# Analog_Controller_PCB.net
KiCad netlist of a schematic drawn in EAGLE
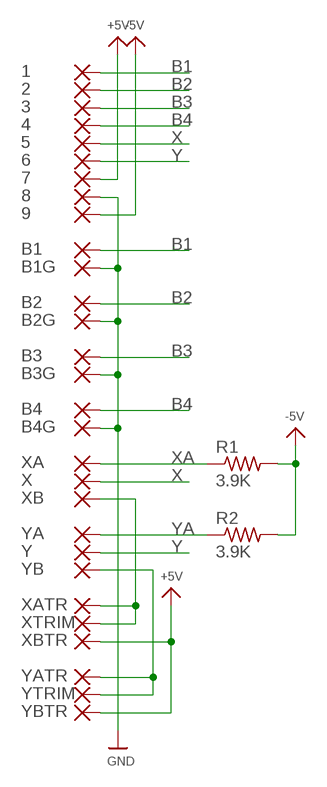
[diagram p0: schematic, sheet 1]

(export (version "E")
  (design (tool "Eeschema 10.0.6"))
  (components
    (comp (ref "1")
      (value "SMD2")
      (footprint "eagle-import:SMD1,27-2,54")
      (libsource (lib "eagle-import") (part "SMD2"))
    )
    (comp (ref "2")
      (value "SMD2")
      (footprint "eagle-import:SMD1,27-2,54")
      (libsource (lib "eagle-import") (part "SMD2"))
    )
    (comp (ref "3")
      (value "SMD2")
      (footprint "eagle-import:SMD1,27-2,54")
      (libsource (lib "eagle-import") (part "SMD2"))
    )
    (comp (ref "4")
      (value "SMD2")
      (footprint "eagle-import:SMD1,27-2,54")
      (libsource (lib "eagle-import") (part "SMD2"))
    )
    (comp (ref "5")
      (value "SMD2")
      (footprint "eagle-import:SMD1,27-2,54")
      (libsource (lib "eagle-import") (part "SMD2"))
    )
    (comp (ref "6")
      (value "SMD2")
      (footprint "eagle-import:SMD1,27-2,54")
      (libsource (lib "eagle-import") (part "SMD2"))
    )
    (comp (ref "7")
      (value "SMD2")
      (footprint "eagle-import:SMD1,27-2,54")
      (libsource (lib "eagle-import") (part "SMD2"))
    )
    (comp (ref "8")
      (value "SMD2")
      (footprint "eagle-import:SMD1,27-2,54")
      (libsource (lib "eagle-import") (part "SMD2"))
    )
    (comp (ref "9")
      (value "SMD2")
      (footprint "eagle-import:SMD1,27-2,54")
      (libsource (lib "eagle-import") (part "SMD2"))
    )
    (comp (ref "B1")
      (value "SMD2")
      (footprint "eagle-import:SMD1,27-2,54")
      (libsource (lib "eagle-import") (part "SMD2"))
    )
    (comp (ref "B1G")
      (value "SMD2")
      (footprint "eagle-import:SMD1,27-2,54")
      (libsource (lib "eagle-import") (part "SMD2"))
    )
    (comp (ref "B2")
      (value "SMD2")
      (footprint "eagle-import:SMD1,27-2,54")
      (libsource (lib "eagle-import") (part "SMD2"))
    )
    (comp (ref "B2G")
      (value "SMD2")
      (footprint "eagle-import:SMD1,27-2,54")
      (libsource (lib "eagle-import") (part "SMD2"))
    )
    (comp (ref "B3")
      (value "SMD2")
      (footprint "eagle-import:SMD1,27-2,54")
      (libsource (lib "eagle-import") (part "SMD2"))
    )
    (comp (ref "B3G")
      (value "SMD2")
      (footprint "eagle-import:SMD1,27-2,54")
      (libsource (lib "eagle-import") (part "SMD2"))
    )
    (comp (ref "B4")
      (value "SMD2")
      (footprint "eagle-import:SMD1,27-2,54")
      (libsource (lib "eagle-import") (part "SMD2"))
    )
    (comp (ref "B4G")
      (value "SMD2")
      (footprint "eagle-import:SMD1,27-2,54")
      (libsource (lib "eagle-import") (part "SMD2"))
    )
    (comp (ref "R1")
      (value "3.9K")
      (footprint "eagle-import:R1206")
      (libsource (lib "eagle-import") (part "R-US_R1206"))
    )
    (comp (ref "R2")
      (value "3.9K")
      (footprint "eagle-import:R1206")
      (libsource (lib "eagle-import") (part "R-US_R1206"))
    )
    (comp (ref "X")
      (value "SMD2")
      (footprint "eagle-import:SMD1,27-2,54")
      (libsource (lib "eagle-import") (part "SMD2"))
    )
    (comp (ref "XA")
      (value "SMD2")
      (footprint "eagle-import:SMD1,27-2,54")
      (libsource (lib "eagle-import") (part "SMD2"))
    )
    (comp (ref "XATR")
      (value "SMD2")
      (footprint "eagle-import:SMD1,27-2,54")
      (libsource (lib "eagle-import") (part "SMD2"))
    )
    (comp (ref "XB")
      (value "SMD2")
      (footprint "eagle-import:SMD1,27-2,54")
      (libsource (lib "eagle-import") (part "SMD2"))
    )
    (comp (ref "XBTR")
      (value "SMD2")
      (footprint "eagle-import:SMD1,27-2,54")
      (libsource (lib "eagle-import") (part "SMD2"))
    )
    (comp (ref "XTRIM")
      (value "SMD2")
      (footprint "eagle-import:SMD1,27-2,54")
      (libsource (lib "eagle-import") (part "SMD2"))
    )
    (comp (ref "Y")
      (value "SMD2")
      (footprint "eagle-import:SMD1,27-2,54")
      (libsource (lib "eagle-import") (part "SMD2"))
    )
    (comp (ref "YA")
      (value "SMD2")
      (footprint "eagle-import:SMD1,27-2,54")
      (libsource (lib "eagle-import") (part "SMD2"))
    )
    (comp (ref "YATR")
      (value "SMD2")
      (footprint "eagle-import:SMD1,27-2,54")
      (libsource (lib "eagle-import") (part "SMD2"))
    )
    (comp (ref "YB")
      (value "SMD2")
      (footprint "eagle-import:SMD1,27-2,54")
      (libsource (lib "eagle-import") (part "SMD2"))
    )
    (comp (ref "YBTR")
      (value "SMD2")
      (footprint "eagle-import:SMD1,27-2,54")
      (libsource (lib "eagle-import") (part "SMD2"))
    )
    (comp (ref "YTRIM")
      (value "SMD2")
      (footprint "eagle-import:SMD1,27-2,54")
      (libsource (lib "eagle-import") (part "SMD2"))
    )
  )
  (nets
    (net (code "1") (name "+5V") (class "Default")
      (node (ref "7") (pin "1") (pinfunction "P_1") (pintype "passive"))
      (node (ref "XBTR") (pin "1") (pinfunction "P_1") (pintype "passive"))
      (node (ref "YBTR") (pin "1") (pinfunction "P_1") (pintype "passive"))
    )
    (net (code "2") (name "-5V") (class "Default")
      (node (ref "9") (pin "1") (pinfunction "P_1") (pintype "passive"))
      (node (ref "R1") (pin "2") (pinfunction "2_2") (pintype "passive"))
      (node (ref "R2") (pin "2") (pinfunction "2_2") (pintype "passive"))
    )
    (net (code "3") (name "/B1") (class "Default")
      (node (ref "1") (pin "1") (pinfunction "P_1") (pintype "passive"))
      (node (ref "B1") (pin "1") (pinfunction "P_1") (pintype "passive"))
    )
    (net (code "4") (name "/B2") (class "Default")
      (node (ref "2") (pin "1") (pinfunction "P_1") (pintype "passive"))
      (node (ref "B2") (pin "1") (pinfunction "P_1") (pintype "passive"))
    )
    (net (code "5") (name "/B3") (class "Default")
      (node (ref "3") (pin "1") (pinfunction "P_1") (pintype "passive"))
      (node (ref "B3") (pin "1") (pinfunction "P_1") (pintype "passive"))
    )
    (net (code "6") (name "/B4") (class "Default")
      (node (ref "4") (pin "1") (pinfunction "P_1") (pintype "passive"))
      (node (ref "B4") (pin "1") (pinfunction "P_1") (pintype "passive"))
    )
    (net (code "7") (name "/X") (class "Default")
      (node (ref "5") (pin "1") (pinfunction "P_1") (pintype "passive"))
      (node (ref "X") (pin "1") (pinfunction "P_1") (pintype "passive"))
    )
    (net (code "8") (name "/XA") (class "Default")
      (node (ref "R1") (pin "1") (pinfunction "1_1") (pintype "passive"))
      (node (ref "XA") (pin "1") (pinfunction "P_1") (pintype "passive"))
    )
    (net (code "9") (name "/Y") (class "Default")
      (node (ref "6") (pin "1") (pinfunction "P_1") (pintype "passive"))
      (node (ref "Y") (pin "1") (pinfunction "P_1") (pintype "passive"))
    )
    (net (code "10") (name "/YA") (class "Default")
      (node (ref "R2") (pin "1") (pinfunction "1_1") (pintype "passive"))
      (node (ref "YA") (pin "1") (pinfunction "P_1") (pintype "passive"))
    )
    (net (code "11") (name "GND") (class "Default")
      (node (ref "8") (pin "1") (pinfunction "P_1") (pintype "passive"))
      (node (ref "B1G") (pin "1") (pinfunction "P_1") (pintype "passive"))
      (node (ref "B2G") (pin "1") (pinfunction "P_1") (pintype "passive"))
      (node (ref "B3G") (pin "1") (pinfunction "P_1") (pintype "passive"))
      (node (ref "B4G") (pin "1") (pinfunction "P_1") (pintype "passive"))
    )
    (net (code "12") (name "Net-(XATR-P)") (class "Default")
      (node (ref "XATR") (pin "1") (pinfunction "P_1") (pintype "passive"))
      (node (ref "XB") (pin "1") (pinfunction "P_1") (pintype "passive"))
      (node (ref "XTRIM") (pin "1") (pinfunction "P_1") (pintype "passive"))
    )
    (net (code "13") (name "Net-(YATR-P)") (class "Default")
      (node (ref "YATR") (pin "1") (pinfunction "P_1") (pintype "passive"))
      (node (ref "YB") (pin "1") (pinfunction "P_1") (pintype "passive"))
      (node (ref "YTRIM") (pin "1") (pinfunction "P_1") (pintype "passive"))
    )
  )
)
